# EASY_EDA_PROJECT.net
KiCad netlist of a schematic drawn in EasyEDA
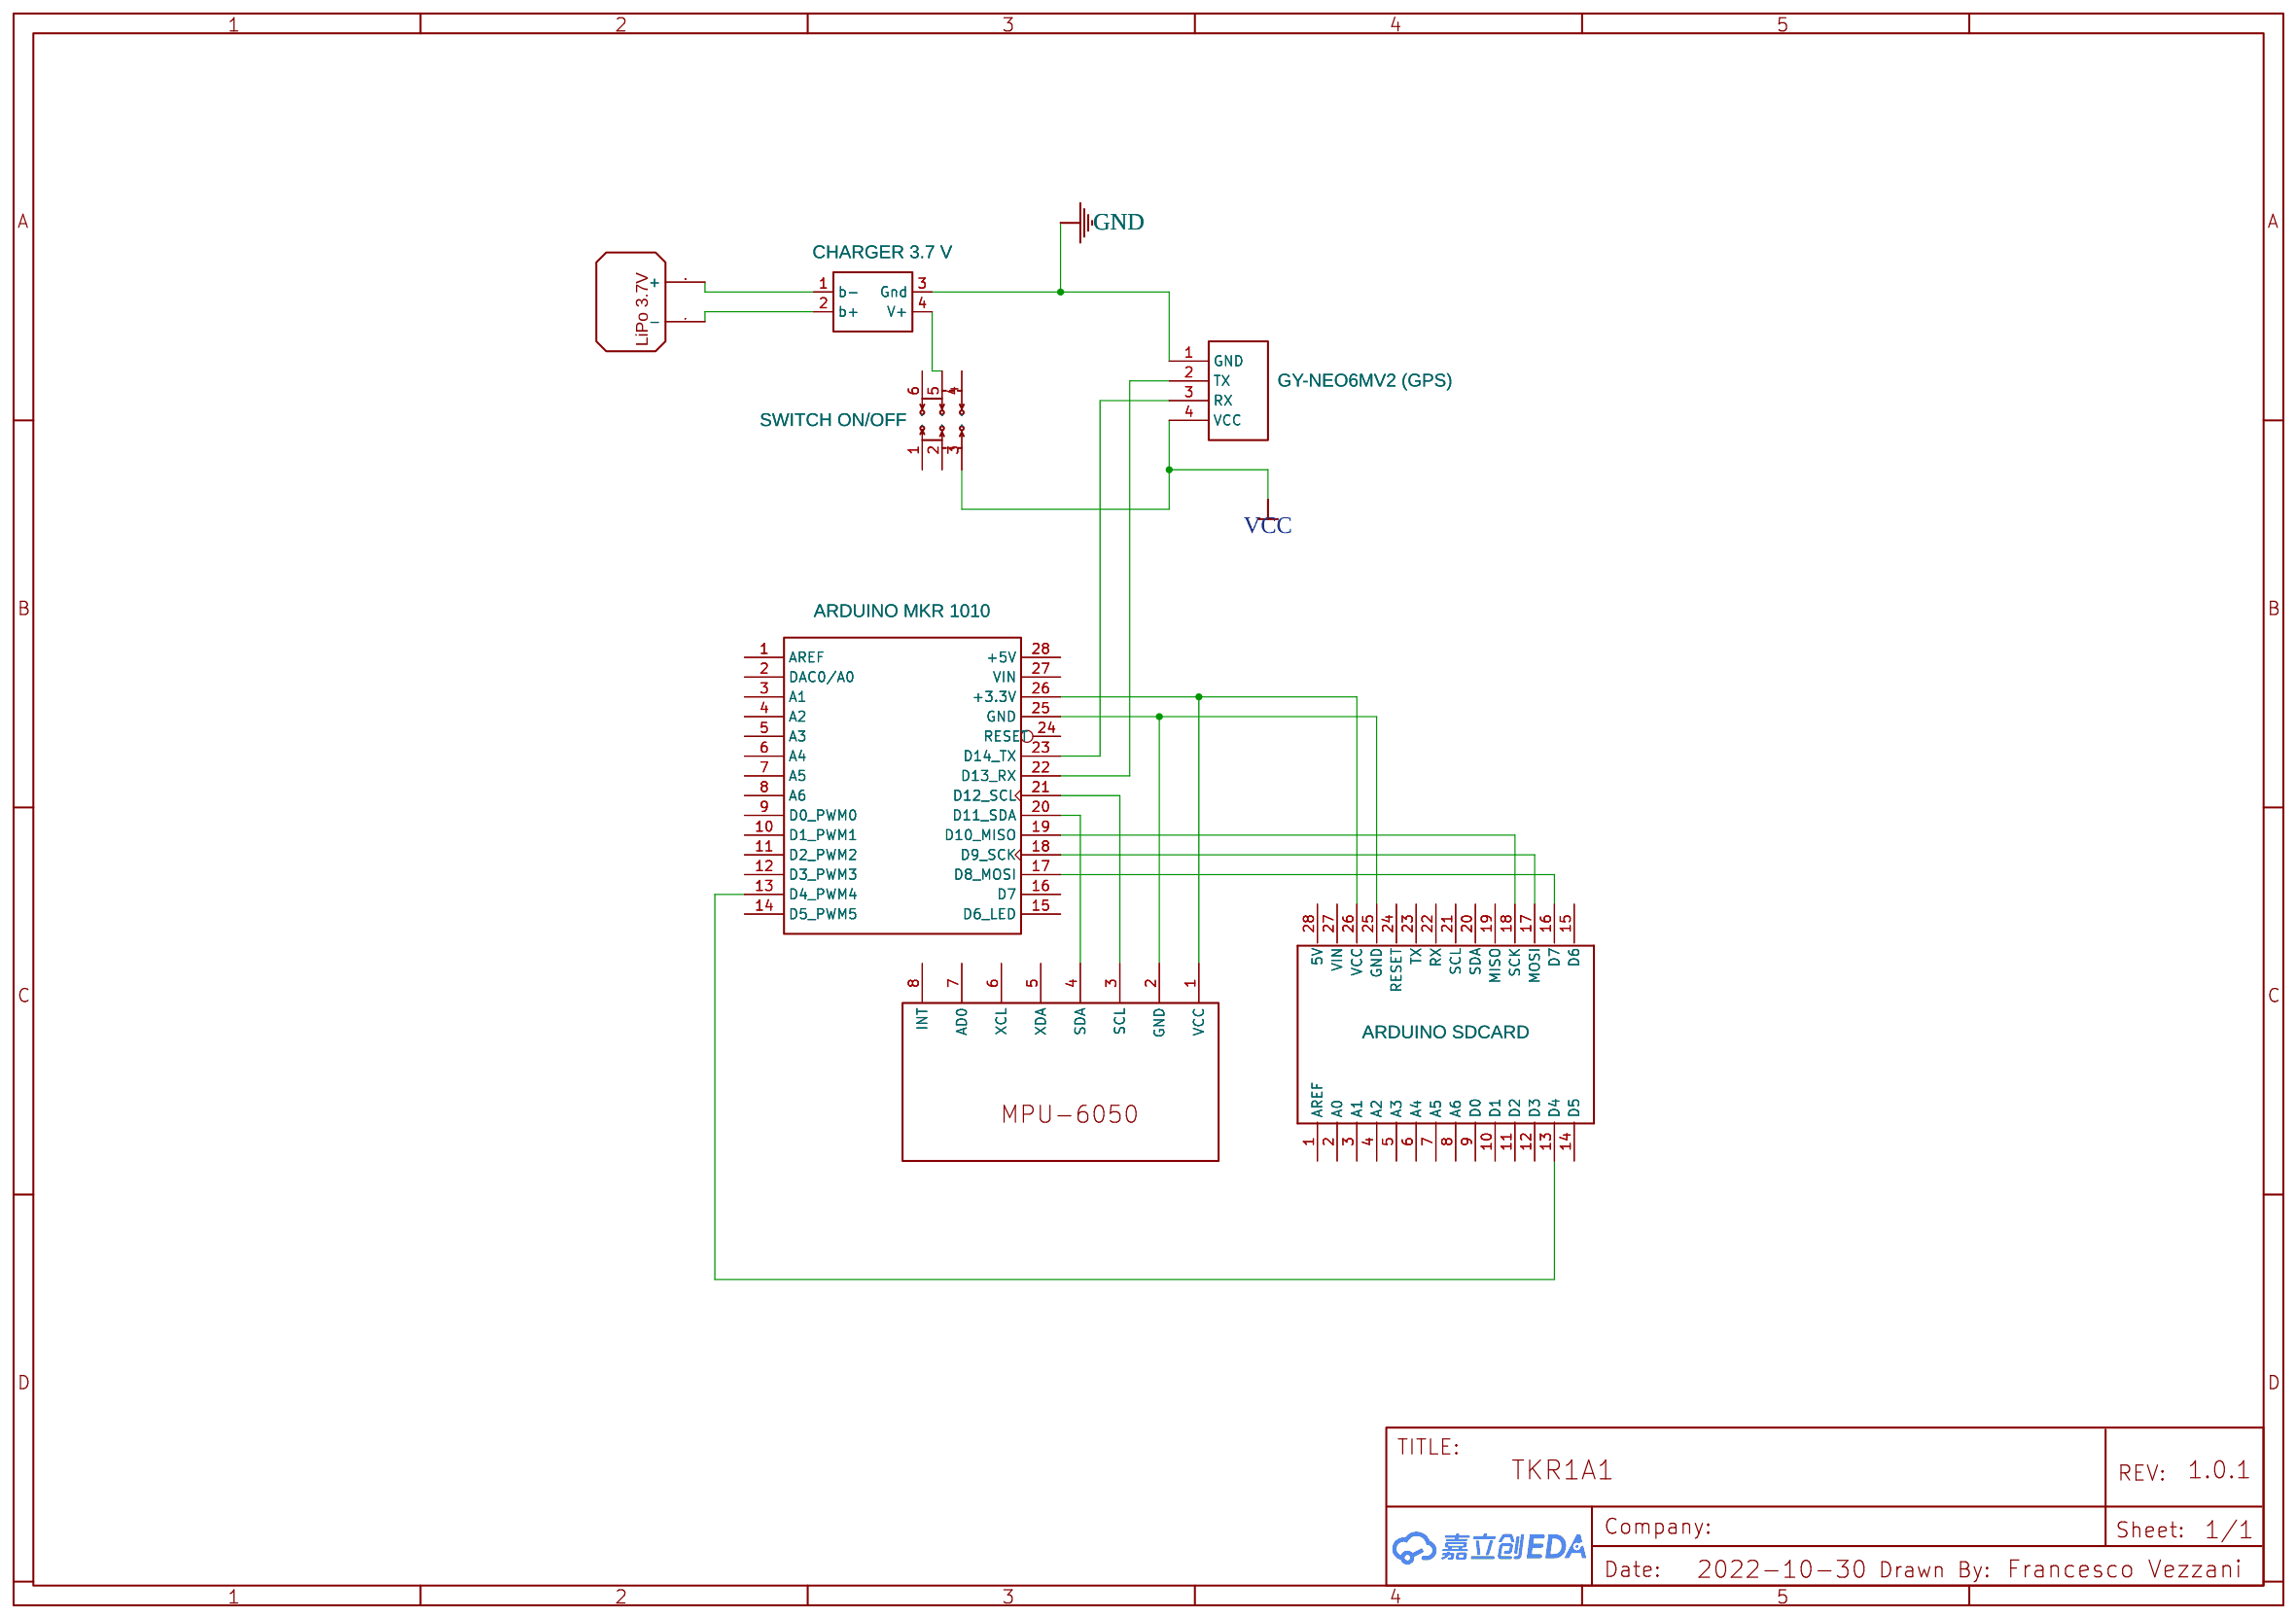
[diagram p0: schematic sheet]

(export (version "E")
  (design (tool "Eeschema 10.0.6"))
  (components
    (comp (ref "CHRAGER1") (value "CHARGER 3.7 V") (libsource (lib "") (part "Battery_Charger_3.7v")))
    (comp (ref "M1")
      (value "ARDUINO MKR 1010")
      (fields (field (name "BOM_Manufacturer Part") "Arduino MKR1000"))
      (libsource (lib "") (part "ARDUINO MKR 1010"))
    )
    (comp (ref "SW1")
      (value "SWITCH ON/OFF")
      (fields
        (field (name "BOM_Manufacturer Part") "SS-22F29-G070")
        (field (name "BOM_Supplier Part") "C2848893")
      )
      (libsource (lib "") (part "SS-22F29-G070"))
    )
    (comp (ref "U2") (value "MPU-6050") (libsource (lib "") (part "MPU-6050")))
    (comp (ref "U3") (value "GY-NEO6MV2 (GPS)") (libsource (lib "") (part "GY-NEO6MV2")))
    (comp (ref "U4") (value "ARDUINO SDCARD") (libsource (lib "") (part "ARDUINO_MKR_BLANK")))
    (comp (ref "U5")
      (value "3.7V 20000MAH LI-PO BATTERY")
      (libsource (lib "") (part "3.7V 500MAH LI-PO BATTERY"))
    )
  )
  (nets
    (net (code "1") (name "GND") (class "Default")
      (node (ref "CHRAGER1") (pin "3") (pinfunction "Gnd_3") (pintype "unspecified"))
      (node (ref "U3") (pin "1") (pinfunction "GND_1") (pintype "passive"))
    )
    (net (code "2") (name "Net-(CHRAGER1-V+)") (class "Default")
      (node (ref "CHRAGER1") (pin "4") (pinfunction "V+_4") (pintype "unspecified"))
      (node (ref "SW1") (pin "5") (pinfunction "5_5") (pintype "unspecified"))
    )
    (net (code "3") (name "Net-(CHRAGER1-b+)") (class "Default")
      (node (ref "CHRAGER1") (pin "2") (pinfunction "b+_2") (pintype "unspecified"))
      (node (ref "U5") (pin "1") (pinfunction "-_1") (pintype "unspecified"))
    )
    (net (code "4") (name "Net-(CHRAGER1-b-)") (class "Default")
      (node (ref "CHRAGER1") (pin "1") (pinfunction "b-_1") (pintype "unspecified"))
      (node (ref "U5") (pin "2") (pinfunction "+_2") (pintype "unspecified"))
    )
    (net (code "5") (name "Net-(M1-+3.3V)") (class "Default")
      (node (ref "M1") (pin "26") (pinfunction "+3.3V_26") (pintype "unspecified"))
      (node (ref "U2") (pin "1") (pinfunction "VCC_1") (pintype "unspecified"))
      (node (ref "U4") (pin "26") (pinfunction "VCC_26") (pintype "bidirectional"))
    )
    (net (code "6") (name "Net-(M1-D4_PWM4)") (class "Default")
      (node (ref "M1") (pin "13") (pinfunction "D4_PWM4_13") (pintype "unspecified"))
      (node (ref "U4") (pin "13") (pinfunction "D4_13") (pintype "bidirectional"))
    )
    (net (code "7") (name "Net-(M1-D8_MOSI)") (class "Default")
      (node (ref "M1") (pin "17") (pinfunction "D8_MOSI_17") (pintype "unspecified"))
      (node (ref "U4") (pin "16") (pinfunction "D7_16") (pintype "bidirectional"))
    )
    (net (code "8") (name "Net-(M1-D9_SCK)") (class "Default")
      (node (ref "M1") (pin "18") (pinfunction "D9_SCK_18") (pintype "unspecified"))
      (node (ref "U4") (pin "17") (pinfunction "MOSI_17") (pintype "bidirectional"))
    )
    (net (code "9") (name "Net-(M1-D10_MISO)") (class "Default")
      (node (ref "M1") (pin "19") (pinfunction "D10_MISO_19") (pintype "unspecified"))
      (node (ref "U4") (pin "18") (pinfunction "SCK_18") (pintype "bidirectional"))
    )
    (net (code "10") (name "Net-(M1-D11_SDA)") (class "Default")
      (node (ref "M1") (pin "20") (pinfunction "D11_SDA_20") (pintype "unspecified"))
      (node (ref "U2") (pin "4") (pinfunction "SDA_4") (pintype "unspecified"))
    )
    (net (code "11") (name "Net-(M1-D12_SCL)") (class "Default")
      (node (ref "M1") (pin "21") (pinfunction "D12_SCL_21") (pintype "unspecified"))
      (node (ref "U2") (pin "3") (pinfunction "SCL_3") (pintype "unspecified"))
    )
    (net (code "12") (name "Net-(M1-D13_RX)") (class "Default")
      (node (ref "M1") (pin "22") (pinfunction "D13_RX_22") (pintype "unspecified"))
      (node (ref "U3") (pin "2") (pinfunction "TX_2") (pintype "output"))
    )
    (net (code "13") (name "Net-(M1-D14_TX)") (class "Default")
      (node (ref "M1") (pin "23") (pinfunction "D14_TX_23") (pintype "unspecified"))
      (node (ref "U3") (pin "3") (pinfunction "RX_3") (pintype "input"))
    )
    (net (code "14") (name "Net-(M1-GND)") (class "Default")
      (node (ref "M1") (pin "25") (pinfunction "GND_25") (pintype "unspecified"))
      (node (ref "U2") (pin "2") (pinfunction "GND_2") (pintype "unspecified"))
      (node (ref "U4") (pin "25") (pinfunction "GND_25") (pintype "bidirectional"))
    )
    (net (code "15") (name "VCC") (class "Default")
      (node (ref "SW1") (pin "3") (pinfunction "3_3") (pintype "unspecified"))
      (node (ref "U3") (pin "4") (pinfunction "VCC_4") (pintype "passive"))
    )
    (net (code "16") (name "unconnected-(M1-+5V-Pad28)") (class "Default")
      (node (ref "M1") (pin "28") (pinfunction "+5V_28") (pintype "unspecified"))
    )
    (net (code "17") (name "unconnected-(M1-A1-Pad3)") (class "Default")
      (node (ref "M1") (pin "3") (pinfunction "A1_3") (pintype "unspecified"))
    )
    (net (code "18") (name "unconnected-(M1-A2-Pad4)") (class "Default")
      (node (ref "M1") (pin "4") (pinfunction "A2_4") (pintype "unspecified"))
    )
    (net (code "19") (name "unconnected-(M1-A3-Pad5)") (class "Default")
      (node (ref "M1") (pin "5") (pinfunction "A3_5") (pintype "unspecified"))
    )
    (net (code "20") (name "unconnected-(M1-A4-Pad6)") (class "Default")
      (node (ref "M1") (pin "6") (pinfunction "A4_6") (pintype "unspecified"))
    )
    (net (code "21") (name "unconnected-(M1-A5-Pad7)") (class "Default")
      (node (ref "M1") (pin "7") (pinfunction "A5_7") (pintype "unspecified"))
    )
    (net (code "22") (name "unconnected-(M1-A6-Pad8)") (class "Default")
      (node (ref "M1") (pin "8") (pinfunction "A6_8") (pintype "unspecified"))
    )
    (net (code "23") (name "unconnected-(M1-AREF-Pad1)") (class "Default")
      (node (ref "M1") (pin "1") (pinfunction "AREF_1") (pintype "unspecified"))
    )
    (net (code "24") (name "unconnected-(M1-D0_PWM0-Pad9)") (class "Default")
      (node (ref "M1") (pin "9") (pinfunction "D0_PWM0_9") (pintype "unspecified"))
    )
    (net (code "25") (name "unconnected-(M1-D1_PWM1-Pad10)") (class "Default")
      (node (ref "M1") (pin "10") (pinfunction "D1_PWM1_10") (pintype "unspecified"))
    )
    (net (code "26") (name "unconnected-(M1-D2_PWM2-Pad11)") (class "Default")
      (node (ref "M1") (pin "11") (pinfunction "D2_PWM2_11") (pintype "unspecified"))
    )
    (net (code "27") (name "unconnected-(M1-D3_PWM3-Pad12)") (class "Default")
      (node (ref "M1") (pin "12") (pinfunction "D3_PWM3_12") (pintype "unspecified"))
    )
    (net (code "28") (name "unconnected-(M1-D5_PWM5-Pad14)") (class "Default")
      (node (ref "M1") (pin "14") (pinfunction "D5_PWM5_14") (pintype "unspecified"))
    )
    (net (code "29") (name "unconnected-(M1-D6_LED-Pad15)") (class "Default")
      (node (ref "M1") (pin "15") (pinfunction "D6_LED_15") (pintype "unspecified"))
    )
    (net (code "30") (name "unconnected-(M1-D7-Pad16)") (class "Default")
      (node (ref "M1") (pin "16") (pinfunction "D7_16") (pintype "unspecified"))
    )
    (net (code "31") (name "unconnected-(M1-DAC0{slash}A0-Pad2)") (class "Default")
      (node (ref "M1") (pin "2") (pinfunction "DAC0/A0_2") (pintype "unspecified"))
    )
    (net (code "32") (name "unconnected-(M1-RESET-Pad24)") (class "Default")
      (node (ref "M1") (pin "24") (pinfunction "RESET_24") (pintype "unspecified"))
    )
    (net (code "33") (name "unconnected-(M1-VIN-Pad27)") (class "Default")
      (node (ref "M1") (pin "27") (pinfunction "VIN_27") (pintype "unspecified"))
    )
    (net (code "34") (name "unconnected-(SW1-Pad1)") (class "Default")
      (node (ref "SW1") (pin "1") (pinfunction "1_1") (pintype "unspecified"))
    )
    (net (code "35") (name "unconnected-(SW1-Pad2)") (class "Default")
      (node (ref "SW1") (pin "2") (pinfunction "2_2") (pintype "unspecified"))
    )
    (net (code "36") (name "unconnected-(SW1-Pad4)") (class "Default")
      (node (ref "SW1") (pin "4") (pinfunction "4_4") (pintype "unspecified"))
    )
    (net (code "37") (name "unconnected-(SW1-Pad6)") (class "Default")
      (node (ref "SW1") (pin "6") (pinfunction "6_6") (pintype "unspecified"))
    )
    (net (code "38") (name "unconnected-(U2-AD0-Pad7)") (class "Default")
      (node (ref "U2") (pin "7") (pinfunction "AD0_7") (pintype "unspecified"))
    )
    (net (code "39") (name "unconnected-(U2-INT-Pad8)") (class "Default")
      (node (ref "U2") (pin "8") (pinfunction "INT_8") (pintype "unspecified"))
    )
    (net (code "40") (name "unconnected-(U2-XCL-Pad6)") (class "Default")
      (node (ref "U2") (pin "6") (pinfunction "XCL_6") (pintype "unspecified"))
    )
    (net (code "41") (name "unconnected-(U2-XDA-Pad5)") (class "Default")
      (node (ref "U2") (pin "5") (pinfunction "XDA_5") (pintype "unspecified"))
    )
    (net (code "42") (name "unconnected-(U4-5V-Pad28)") (class "Default")
      (node (ref "U4") (pin "28") (pinfunction "5V_28") (pintype "bidirectional"))
    )
    (net (code "43") (name "unconnected-(U4-A0-Pad2)") (class "Default")
      (node (ref "U4") (pin "2") (pinfunction "A0_2") (pintype "bidirectional"))
    )
    (net (code "44") (name "unconnected-(U4-A1-Pad3)") (class "Default")
      (node (ref "U4") (pin "3") (pinfunction "A1_3") (pintype "bidirectional"))
    )
    (net (code "45") (name "unconnected-(U4-A2-Pad4)") (class "Default")
      (node (ref "U4") (pin "4") (pinfunction "A2_4") (pintype "bidirectional"))
    )
    (net (code "46") (name "unconnected-(U4-A3-Pad5)") (class "Default")
      (node (ref "U4") (pin "5") (pinfunction "A3_5") (pintype "bidirectional"))
    )
    (net (code "47") (name "unconnected-(U4-A4-Pad6)") (class "Default")
      (node (ref "U4") (pin "6") (pinfunction "A4_6") (pintype "bidirectional"))
    )
    (net (code "48") (name "unconnected-(U4-A5-Pad7)") (class "Default")
      (node (ref "U4") (pin "7") (pinfunction "A5_7") (pintype "bidirectional"))
    )
    (net (code "49") (name "unconnected-(U4-A6-Pad8)") (class "Default")
      (node (ref "U4") (pin "8") (pinfunction "A6_8") (pintype "bidirectional"))
    )
    (net (code "50") (name "unconnected-(U4-AREF-Pad1)") (class "Default")
      (node (ref "U4") (pin "1") (pinfunction "AREF_1") (pintype "bidirectional"))
    )
    (net (code "51") (name "unconnected-(U4-D0-Pad9)") (class "Default")
      (node (ref "U4") (pin "9") (pinfunction "D0_9") (pintype "bidirectional"))
    )
    (net (code "52") (name "unconnected-(U4-D1-Pad10)") (class "Default")
      (node (ref "U4") (pin "10") (pinfunction "D1_10") (pintype "bidirectional"))
    )
    (net (code "53") (name "unconnected-(U4-D2-Pad11)") (class "Default")
      (node (ref "U4") (pin "11") (pinfunction "D2_11") (pintype "bidirectional"))
    )
    (net (code "54") (name "unconnected-(U4-D3-Pad12)") (class "Default")
      (node (ref "U4") (pin "12") (pinfunction "D3_12") (pintype "bidirectional"))
    )
    (net (code "55") (name "unconnected-(U4-D5-Pad14)") (class "Default")
      (node (ref "U4") (pin "14") (pinfunction "D5_14") (pintype "bidirectional"))
    )
    (net (code "56") (name "unconnected-(U4-D6-Pad15)") (class "Default")
      (node (ref "U4") (pin "15") (pinfunction "D6_15") (pintype "bidirectional"))
    )
    (net (code "57") (name "unconnected-(U4-MISO-Pad19)") (class "Default")
      (node (ref "U4") (pin "19") (pinfunction "MISO_19") (pintype "bidirectional"))
    )
    (net (code "58") (name "unconnected-(U4-RESET-Pad24)") (class "Default")
      (node (ref "U4") (pin "24") (pinfunction "RESET_24") (pintype "bidirectional"))
    )
    (net (code "59") (name "unconnected-(U4-RX-Pad22)") (class "Default")
      (node (ref "U4") (pin "22") (pinfunction "RX_22") (pintype "bidirectional"))
    )
    (net (code "60") (name "unconnected-(U4-SCL-Pad21)") (class "Default")
      (node (ref "U4") (pin "21") (pinfunction "SCL_21") (pintype "bidirectional"))
    )
    (net (code "61") (name "unconnected-(U4-SDA-Pad20)") (class "Default")
      (node (ref "U4") (pin "20") (pinfunction "SDA_20") (pintype "bidirectional"))
    )
    (net (code "62") (name "unconnected-(U4-TX-Pad23)") (class "Default")
      (node (ref "U4") (pin "23") (pinfunction "TX_23") (pintype "bidirectional"))
    )
    (net (code "63") (name "unconnected-(U4-VIN-Pad27)") (class "Default")
      (node (ref "U4") (pin "27") (pinfunction "VIN_27") (pintype "bidirectional"))
    )
  )
)
